# processor.net
KiCad netlist of a schematic drawn in Altium Designer
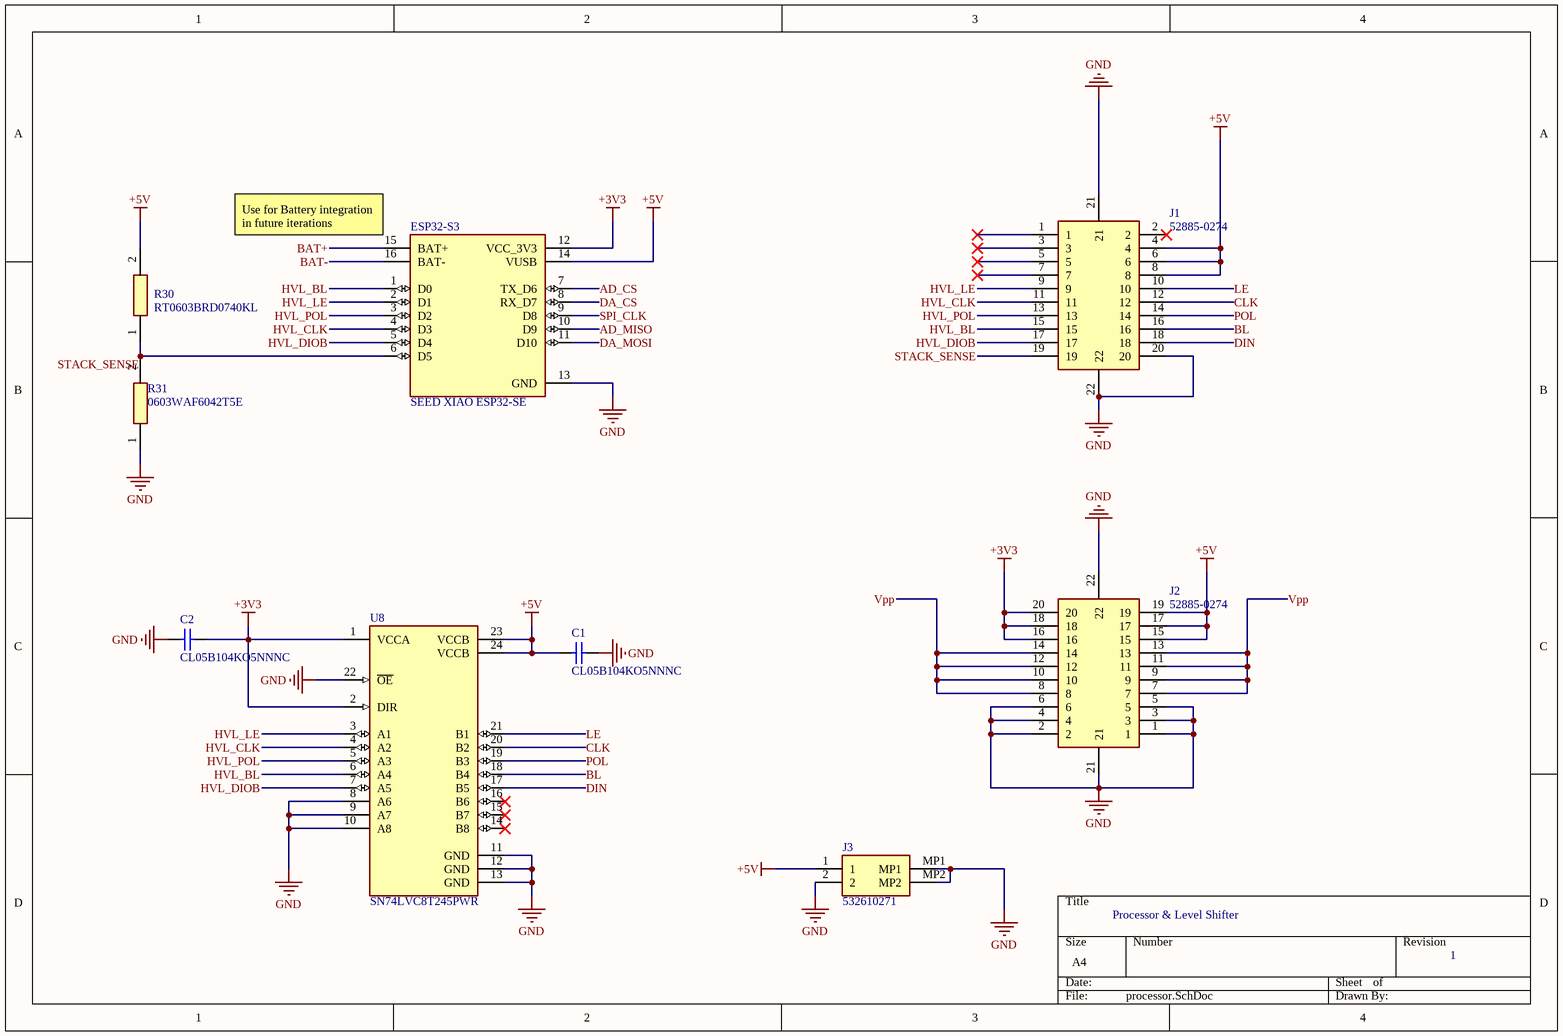
[diagram p0: processor.SchDoc]

(export (version "E")
  (design (tool "Eeschema 10.0.6"))
  (components
    (comp (ref "C1")
      (value "CL05B104KO5NNNC")
      (footprint "CAPC1050X55X23ML05T13")
      (description "Chip Capacitor, 100 nF, +/- 10%, 16 V, -55 to 125 degC, 0402 (1005 Metric), RoHS, Tape and Reel")
      (fields (field (name "MANUFACTURER") "Samsung Electro-Mechanics"))
      (libsource (lib "Altium Content Vault") (part "CAP-NP-2"))
    )
    (comp (ref "C2")
      (value "CL05B104KO5NNNC")
      (footprint "CAPC1050X55X23ML05T13")
      (description "Chip Capacitor, 100 nF, +/- 10%, 16 V, -55 to 125 degC, 0402 (1005 Metric), RoHS, Tape and Reel")
      (fields (field (name "MANUFACTURER") "Samsung Electro-Mechanics"))
      (libsource (lib "Altium Content Vault") (part "CAP-NP-2"))
    )
    (comp (ref "ESP32-S3")
      (value "SEED XIAO ESP32-SE")
      (footprint "PCBComponent_1")
      (libsource (lib "ESP32-S3") (part "Component_1"))
    )
    (comp (ref "J1")
      (value "52885-0274")
      (footprint "SamacSys:528850274")
      (description "Connector")
      (fields (field (name "MOUSER PART NUMBER") "538-52885-0274"))
      (libsource (lib "") (part "52885-0274_1"))
    )
    (comp (ref "J2")
      (value "52885-0274")
      (footprint "SamacSys:528850274")
      (description "Connector")
      (fields (field (name "MOUSER PART NUMBER") "538-52885-0274"))
      (libsource (lib "*") (part "52885-0274"))
    )
    (comp (ref "J3")
      (value "532610271")
      (footprint "SamacSys:532610271")
      (description "C177225")
      (fields
        (field (name "MANUFACTURER_PART_NUMBER") "53261-0271")
        (field (name "MOUSER PART NUMBER") "538-53261-0271")
      )
      (libsource (lib "*") (part "53261-0271"))
    )
    (comp (ref "R30")
      (value "RT0603BRD0740KL")
      (footprint "SamacSys:RESC1608X55N")
      (description "Resistor")
      (fields (field (name "MOUSER PART NUMBER") "603-RT0603BRD0740KL"))
      (libsource (lib "*") (part "RT0603BRD0740KL"))
    )
    (comp (ref "R31")
      (value "0603WAF6042T5E")
      (footprint "SamacSys:RESC1608X55N")
      (description "Resistor")
      (libsource (lib "*") (part "MCT06030C6042FP500"))
    )
    (comp (ref "U8")
      (value "SN74LVC8T245PWR")
      (footprint "FP-PW0024A-MFG")
      (description "IC TRNSLTR BIDIRECTIONAL 24TSSOP")
      (fields
        (field (name "OCTOPART") "https://octopart.com/sn74lvc8t245pwr-texas+instruments-517164")
        (field (name "MANUFACTURER") "Texas Instruments")
      )
      (libsource (lib "Altium Content Vault") (part "51221a7e4c45eff2cf920f7ccaf63e0"))
    )
  )
  (nets
    (net (code "1") (name "+3V3") (class "Default")
      (node (ref "C2") (pin "2") (pinfunction "2_2") (pintype "passive"))
      (node (ref "ESP32-S3") (pin "12") (pinfunction "VCC_3V3_12") (pintype "power_in"))
      (node (ref "J2") (pin "16") (pinfunction "16_16") (pintype "passive"))
      (node (ref "J2") (pin "18") (pinfunction "18_18") (pintype "passive"))
      (node (ref "J2") (pin "20") (pinfunction "20_20") (pintype "passive"))
      (node (ref "U8") (pin "1") (pinfunction "VCCA_1") (pintype "power_in"))
      (node (ref "U8") (pin "2") (pinfunction "DIR_2") (pintype "input"))
    )
    (net (code "2") (name "+5V") (class "Default")
      (node (ref "C1") (pin "1") (pinfunction "1_1") (pintype "passive"))
      (node (ref "ESP32-S3") (pin "14") (pinfunction "VUSB_14") (pintype "power_in"))
      (node (ref "J1") (pin "4") (pinfunction "4_4") (pintype "passive"))
      (node (ref "J1") (pin "6") (pinfunction "6_6") (pintype "passive"))
      (node (ref "J1") (pin "8") (pinfunction "8_8") (pintype "passive"))
      (node (ref "J2") (pin "15") (pinfunction "15_15") (pintype "passive"))
      (node (ref "J2") (pin "17") (pinfunction "17_17") (pintype "passive"))
      (node (ref "J2") (pin "19") (pinfunction "19_19") (pintype "passive"))
      (node (ref "J3") (pin "1") (pinfunction "1_1") (pintype "passive"))
      (node (ref "R30") (pin "2") (pinfunction "2_2") (pintype "passive"))
      (node (ref "U8") (pin "23") (pinfunction "VCCB_23") (pintype "power_in"))
      (node (ref "U8") (pin "24") (pinfunction "VCCB_24") (pintype "power_in"))
    )
    (net (code "3") (name "/AD_CS") (class "Default")
      (node (ref "ESP32-S3") (pin "7") (pinfunction "TX_D6_7") (pintype "bidirectional"))
    )
    (net (code "4") (name "/AD_MISO") (class "Default")
      (node (ref "ESP32-S3") (pin "10") (pinfunction "D9_10") (pintype "bidirectional"))
    )
    (net (code "5") (name "/BAT+") (class "Default")
      (node (ref "ESP32-S3") (pin "15") (pinfunction "BAT+_15") (pintype "passive"))
    )
    (net (code "6") (name "/BAT-") (class "Default")
      (node (ref "ESP32-S3") (pin "16") (pinfunction "BAT-_16") (pintype "passive"))
    )
    (net (code "7") (name "/BL") (class "Default")
      (node (ref "J1") (pin "16") (pinfunction "16_16") (pintype "passive"))
      (node (ref "U8") (pin "18") (pinfunction "B4_18") (pintype "bidirectional"))
    )
    (net (code "8") (name "/CLK") (class "Default")
      (node (ref "J1") (pin "12") (pinfunction "12_12") (pintype "passive"))
      (node (ref "U8") (pin "20") (pinfunction "B2_20") (pintype "bidirectional"))
    )
    (net (code "9") (name "/DA_CS") (class "Default")
      (node (ref "ESP32-S3") (pin "8") (pinfunction "RX_D7_8") (pintype "bidirectional"))
    )
    (net (code "10") (name "/DA_MOSI") (class "Default")
      (node (ref "ESP32-S3") (pin "11") (pinfunction "D10_11") (pintype "bidirectional"))
    )
    (net (code "11") (name "/DIN") (class "Default")
      (node (ref "J1") (pin "18") (pinfunction "18_18") (pintype "passive"))
      (node (ref "U8") (pin "17") (pinfunction "B5_17") (pintype "bidirectional"))
    )
    (net (code "12") (name "/HVL_BL") (class "Default")
      (node (ref "ESP32-S3") (pin "1") (pinfunction "D0_1") (pintype "bidirectional"))
      (node (ref "J1") (pin "15") (pinfunction "15_15") (pintype "passive"))
      (node (ref "U8") (pin "6") (pinfunction "A4_6") (pintype "bidirectional"))
    )
    (net (code "13") (name "/HVL_CLK") (class "Default")
      (node (ref "ESP32-S3") (pin "4") (pinfunction "D3_4") (pintype "bidirectional"))
      (node (ref "J1") (pin "11") (pinfunction "11_11") (pintype "passive"))
      (node (ref "U8") (pin "4") (pinfunction "A2_4") (pintype "bidirectional"))
    )
    (net (code "14") (name "/HVL_DIOB") (class "Default")
      (node (ref "ESP32-S3") (pin "5") (pinfunction "D4_5") (pintype "bidirectional"))
      (node (ref "J1") (pin "17") (pinfunction "17_17") (pintype "passive"))
      (node (ref "U8") (pin "7") (pinfunction "A5_7") (pintype "bidirectional"))
    )
    (net (code "15") (name "/HVL_LE") (class "Default")
      (node (ref "ESP32-S3") (pin "2") (pinfunction "D1_2") (pintype "bidirectional"))
      (node (ref "J1") (pin "9") (pinfunction "9_9") (pintype "passive"))
      (node (ref "U8") (pin "3") (pinfunction "A1_3") (pintype "bidirectional"))
    )
    (net (code "16") (name "/HVL_POL") (class "Default")
      (node (ref "ESP32-S3") (pin "3") (pinfunction "D2_3") (pintype "bidirectional"))
      (node (ref "J1") (pin "13") (pinfunction "13_13") (pintype "passive"))
      (node (ref "U8") (pin "5") (pinfunction "A3_5") (pintype "bidirectional"))
    )
    (net (code "17") (name "/LE") (class "Default")
      (node (ref "J1") (pin "10") (pinfunction "10_10") (pintype "passive"))
      (node (ref "U8") (pin "21") (pinfunction "B1_21") (pintype "bidirectional"))
    )
    (net (code "18") (name "/POL") (class "Default")
      (node (ref "J1") (pin "14") (pinfunction "14_14") (pintype "passive"))
      (node (ref "U8") (pin "19") (pinfunction "B3_19") (pintype "bidirectional"))
    )
    (net (code "19") (name "/SPI_CLK") (class "Default")
      (node (ref "ESP32-S3") (pin "9") (pinfunction "D8_9") (pintype "bidirectional"))
    )
    (net (code "20") (name "/STACK_SENSE") (class "Default")
      (node (ref "ESP32-S3") (pin "6") (pinfunction "D5_6") (pintype "bidirectional"))
      (node (ref "J1") (pin "19") (pinfunction "19_19") (pintype "passive"))
      (node (ref "R30") (pin "1") (pinfunction "1_1") (pintype "passive"))
      (node (ref "R31") (pin "2") (pinfunction "2_2") (pintype "passive"))
    )
    (net (code "21") (name "/Vpp") (class "Default")
      (node (ref "J2") (pin "10") (pinfunction "10_10") (pintype "passive"))
      (node (ref "J2") (pin "11") (pinfunction "11_11") (pintype "passive"))
      (node (ref "J2") (pin "12") (pinfunction "12_12") (pintype "passive"))
      (node (ref "J2") (pin "13") (pinfunction "13_13") (pintype "passive"))
      (node (ref "J2") (pin "14") (pinfunction "14_14") (pintype "passive"))
      (node (ref "J2") (pin "7") (pinfunction "7_7") (pintype "passive"))
      (node (ref "J2") (pin "8") (pinfunction "8_8") (pintype "passive"))
      (node (ref "J2") (pin "9") (pinfunction "9_9") (pintype "passive"))
    )
    (net (code "22") (name "GND") (class "Default")
      (node (ref "C1") (pin "2") (pinfunction "2_2") (pintype "passive"))
      (node (ref "C2") (pin "1") (pinfunction "1_1") (pintype "passive"))
      (node (ref "ESP32-S3") (pin "13") (pinfunction "GND_13") (pintype "power_in"))
      (node (ref "J1") (pin "20") (pinfunction "20_20") (pintype "passive"))
      (node (ref "J1") (pin "21") (pinfunction "21_21") (pintype "passive"))
      (node (ref "J1") (pin "22") (pinfunction "22_22") (pintype "passive"))
      (node (ref "J2") (pin "1") (pinfunction "1_1") (pintype "passive"))
      (node (ref "J2") (pin "2") (pinfunction "2_2") (pintype "passive"))
      (node (ref "J2") (pin "21") (pinfunction "21_21") (pintype "passive"))
      (node (ref "J2") (pin "22") (pinfunction "22_22") (pintype "passive"))
      (node (ref "J2") (pin "3") (pinfunction "3_3") (pintype "passive"))
      (node (ref "J2") (pin "4") (pinfunction "4_4") (pintype "passive"))
      (node (ref "J2") (pin "5") (pinfunction "5_5") (pintype "passive"))
      (node (ref "J2") (pin "6") (pinfunction "6_6") (pintype "passive"))
      (node (ref "J3") (pin "2") (pinfunction "2_2") (pintype "passive"))
      (node (ref "J3") (pin "MP1") (pinfunction "MP1_MP1") (pintype "passive"))
      (node (ref "J3") (pin "MP2") (pinfunction "MP2_MP2") (pintype "passive"))
      (node (ref "R31") (pin "1") (pinfunction "1_1") (pintype "passive"))
      (node (ref "U8") (pin "10") (pinfunction "A8_10") (pintype "passive"))
      (node (ref "U8") (pin "11") (pinfunction "GND_11") (pintype "power_in"))
      (node (ref "U8") (pin "12") (pinfunction "GND_12") (pintype "power_in"))
      (node (ref "U8") (pin "13") (pinfunction "GND_13") (pintype "power_in"))
      (node (ref "U8") (pin "22") (pinfunction "~{OE}_22") (pintype "input"))
      (node (ref "U8") (pin "8") (pinfunction "A6_8") (pintype "passive"))
      (node (ref "U8") (pin "9") (pinfunction "A7_9") (pintype "passive"))
    )
    (net (code "23") (name "unconnected-(J1-Pad1)") (class "Default")
      (node (ref "J1") (pin "1") (pinfunction "1_1") (pintype "passive+no_connect"))
    )
    (net (code "24") (name "unconnected-(J1-Pad2)") (class "Default")
      (node (ref "J1") (pin "2") (pinfunction "2_2") (pintype "passive+no_connect"))
    )
    (net (code "25") (name "unconnected-(J1-Pad3)") (class "Default")
      (node (ref "J1") (pin "3") (pinfunction "3_3") (pintype "passive+no_connect"))
    )
    (net (code "26") (name "unconnected-(J1-Pad5)") (class "Default")
      (node (ref "J1") (pin "5") (pinfunction "5_5") (pintype "passive+no_connect"))
    )
    (net (code "27") (name "unconnected-(J1-Pad7)") (class "Default")
      (node (ref "J1") (pin "7") (pinfunction "7_7") (pintype "passive+no_connect"))
    )
    (net (code "28") (name "unconnected-(U8-B6-Pad16)") (class "Default")
      (node (ref "U8") (pin "16") (pinfunction "B6_16") (pintype "bidirectional+no_connect"))
    )
    (net (code "29") (name "unconnected-(U8-B7-Pad15)") (class "Default")
      (node (ref "U8") (pin "15") (pinfunction "B7_15") (pintype "bidirectional+no_connect"))
    )
    (net (code "30") (name "unconnected-(U8-B8-Pad14)") (class "Default")
      (node (ref "U8") (pin "14") (pinfunction "B8_14") (pintype "bidirectional+no_connect"))
    )
  )
)
